# IFB-40003-R01_-_I2C_Buttons.net
KiCad netlist of a schematic drawn in EAGLE
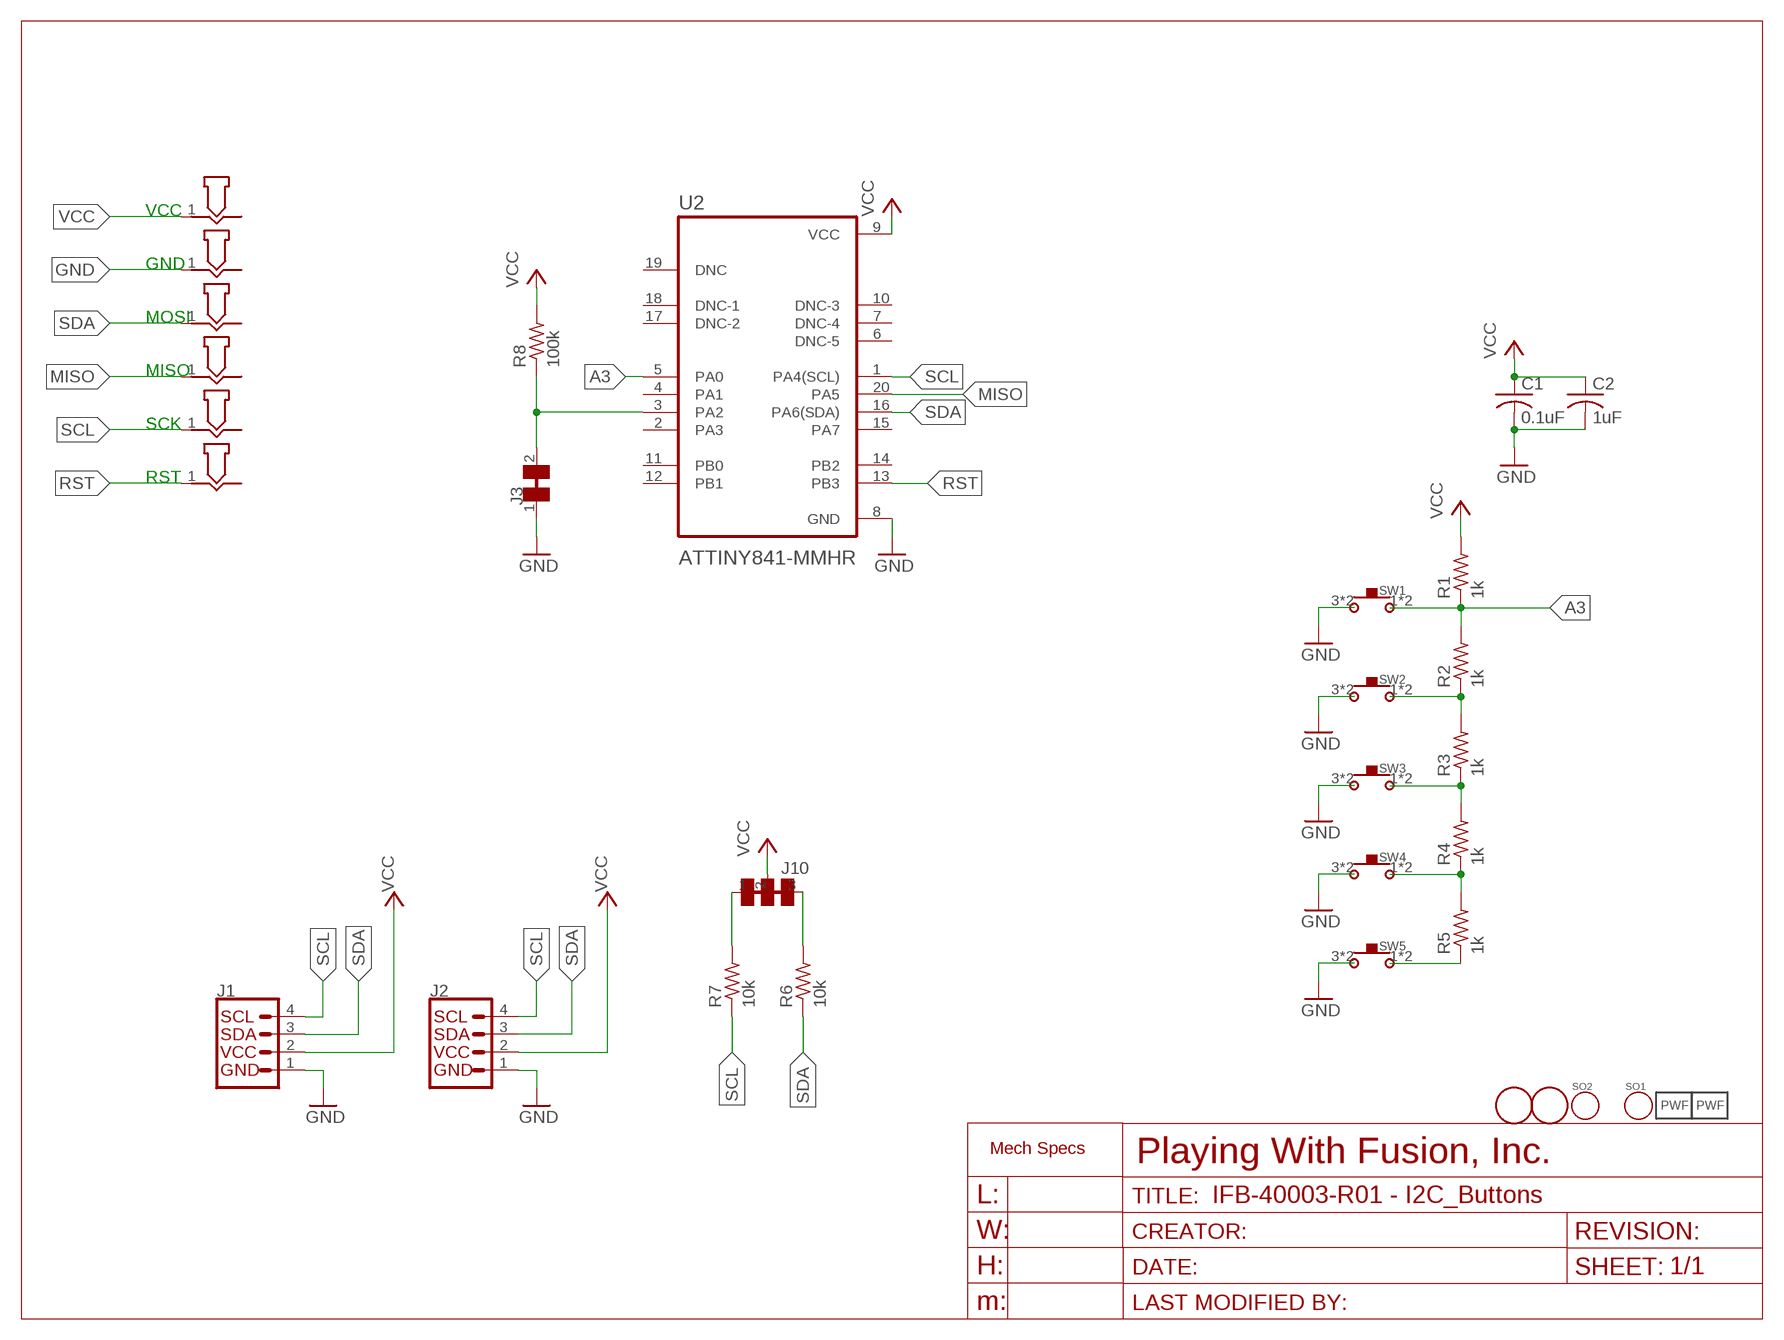
[diagram p0: schematic, sheet 1]

(export (version "E")
  (design (tool "Eeschema 10.0.6"))
  (components
    (comp (ref "C1")
      (value "0.1uF")
      (footprint "eagle-import:C0603K")
      (libsource (lib "eagle-import") (part "C-USC0603K"))
    )
    (comp (ref "C2")
      (value "1uF")
      (footprint "eagle-import:C0603K")
      (libsource (lib "eagle-import") (part "C-USC0603K"))
    )
    (comp (ref "J1")
      (value "QWIIC_CONNECTORJS-1MM")
      (footprint "eagle-import:1X04_1MM_RA")
      (libsource (lib "eagle-import") (part "QWIIC_CONNECTORJS-1MM"))
    )
    (comp (ref "J2")
      (value "QWIIC_CONNECTORJS-1MM")
      (footprint "eagle-import:1X04_1MM_RA")
      (libsource (lib "eagle-import") (part "QWIIC_CONNECTORJS-1MM"))
    )
    (comp (ref "J3")
      (value "CUTTABLE_JUMPER")
      (footprint "eagle-import:SMT_CUTTABLE_JUMPER")
      (libsource (lib "eagle-import") (part "CUTTABLE_JUMPER"))
    )
    (comp (ref "J4")
      (value "POGO_PAD")
      (footprint "eagle-import:P50_POGO_BOARD_CONTACT_12MIL")
      (libsource (lib "eagle-import") (part "POGO_PAD"))
    )
    (comp (ref "J5")
      (value "POGO_PAD")
      (footprint "eagle-import:P50_POGO_BOARD_CONTACT_12MIL")
      (libsource (lib "eagle-import") (part "POGO_PAD"))
    )
    (comp (ref "J6")
      (value "POGO_PAD")
      (footprint "eagle-import:P50_POGO_BOARD_CONTACT_12MIL")
      (libsource (lib "eagle-import") (part "POGO_PAD"))
    )
    (comp (ref "J7")
      (value "POGO_PAD")
      (footprint "eagle-import:P50_POGO_BOARD_CONTACT_12MIL")
      (libsource (lib "eagle-import") (part "POGO_PAD"))
    )
    (comp (ref "J8")
      (value "POGO_PAD")
      (footprint "eagle-import:P50_POGO_BOARD_CONTACT_12MIL")
      (libsource (lib "eagle-import") (part "POGO_PAD"))
    )
    (comp (ref "J9")
      (value "POGO_PAD")
      (footprint "eagle-import:P50_POGO_BOARD_CONTACT_12MIL")
      (libsource (lib "eagle-import") (part "POGO_PAD"))
    )
    (comp (ref "J10")
      (value "CUT_JUMPER_2X")
      (footprint "eagle-import:SMT_2X_CUTTABLE_JUMPER")
      (libsource (lib "eagle-import") (part "CUT_JUMPER_2X"))
    )
    (comp (ref "LOGO1")
      (value "PWF_LOGOPWF-6MM-SS")
      (footprint "eagle-import:LOGO_6MM_STEIN")
      (libsource (lib "eagle-import") (part "PWF_LOGOPWF-6MM-SS"))
    )
    (comp (ref "LOGO2")
      (value "PWF_LOGOPWF-12MM-SS")
      (footprint "eagle-import:LOGO_12MM_STEIN")
      (libsource (lib "eagle-import") (part "PWF_LOGOPWF-12MM-SS"))
    )
    (comp (ref "R1")
      (value "1k")
      (footprint "eagle-import:R0603")
      (libsource (lib "eagle-import") (part "R-US_R0603"))
    )
    (comp (ref "R2")
      (value "1k")
      (footprint "eagle-import:R0603")
      (libsource (lib "eagle-import") (part "R-US_R0603"))
    )
    (comp (ref "R3")
      (value "1k")
      (footprint "eagle-import:R0603")
      (libsource (lib "eagle-import") (part "R-US_R0603"))
    )
    (comp (ref "R4")
      (value "1k")
      (footprint "eagle-import:R0603")
      (libsource (lib "eagle-import") (part "R-US_R0603"))
    )
    (comp (ref "R5")
      (value "1k")
      (footprint "eagle-import:R0603")
      (libsource (lib "eagle-import") (part "R-US_R0603"))
    )
    (comp (ref "R6")
      (value "10k")
      (footprint "eagle-import:R0603")
      (libsource (lib "eagle-import") (part "R-US_R0603"))
    )
    (comp (ref "R7")
      (value "10k")
      (footprint "eagle-import:R0603")
      (libsource (lib "eagle-import") (part "R-US_R0603"))
    )
    (comp (ref "R8")
      (value "100k")
      (footprint "eagle-import:R0603")
      (libsource (lib "eagle-import") (part "R-US_R0603"))
    )
    (comp (ref "SO1")
      (value "STAND_OFFNO4_TIGHT")
      (footprint "eagle-import:STANDOFF_NO4_TIGHT")
      (libsource (lib "eagle-import") (part "STAND_OFFNO4_TIGHT"))
    )
    (comp (ref "SO2")
      (value "STAND_OFFNO4_TIGHT")
      (footprint "eagle-import:STANDOFF_NO4_TIGHT")
      (libsource (lib "eagle-import") (part "STAND_OFFNO4_TIGHT"))
    )
    (comp (ref "SW1")
      (value "PTS6455MM")
      (footprint "eagle-import:PTS645_5MM")
      (libsource (lib "eagle-import") (part "PTS6455MM"))
    )
    (comp (ref "SW2")
      (value "PTS6455MM")
      (footprint "eagle-import:PTS645_5MM")
      (libsource (lib "eagle-import") (part "PTS6455MM"))
    )
    (comp (ref "SW3")
      (value "PTS6455MM")
      (footprint "eagle-import:PTS645_5MM")
      (libsource (lib "eagle-import") (part "PTS6455MM"))
    )
    (comp (ref "SW4")
      (value "PTS6455MM")
      (footprint "eagle-import:PTS645_5MM")
      (libsource (lib "eagle-import") (part "PTS6455MM"))
    )
    (comp (ref "SW5")
      (value "PTS6455MM")
      (footprint "eagle-import:PTS645_5MM")
      (libsource (lib "eagle-import") (part "PTS6455MM"))
    )
    (comp (ref "U$2")
      (value "FIDUCIAL")
      (footprint "eagle-import:FIDUCIAL_1MM")
      (libsource (lib "eagle-import") (part "FIDUCIAL"))
    )
    (comp (ref "U$3")
      (value "FIDUCIAL")
      (footprint "eagle-import:FIDUCIAL_1MM")
      (libsource (lib "eagle-import") (part "FIDUCIAL"))
    )
    (comp (ref "U2")
      (value "ATTINY841-MMHR")
      (footprint "eagle-import:QFN45P300X300X85-21N")
      (fields (field (name "MF") "Microchip"))
      (libsource (lib "eagle-import") (part "ATTINY841-MMHR"))
    )
  )
  (nets
    (net (code "1") (name "A3") (class "Default")
      (node (ref "R1") (pin "1") (pinfunction "1_1") (pintype "passive"))
      (node (ref "R2") (pin "2") (pinfunction "2_2") (pintype "passive"))
      (node (ref "SW1") (pin "1") (pinfunction "1_1") (pintype "bidirectional"))
      (node (ref "SW1") (pin "2") (pinfunction "1_2") (pintype "bidirectional"))
      (node (ref "U2") (pin "5") (pinfunction "PA0_5") (pintype "bidirectional"))
    )
    (net (code "2") (name "GND") (class "Default")
      (node (ref "C1") (pin "2") (pinfunction "2_2") (pintype "passive"))
      (node (ref "C2") (pin "2") (pinfunction "2_2") (pintype "passive"))
      (node (ref "J1") (pin "1") (pinfunction "GND_1") (pintype "power_in"))
      (node (ref "J2") (pin "1") (pinfunction "GND_1") (pintype "power_in"))
      (node (ref "J3") (pin "1") (pinfunction "1_1") (pintype "bidirectional"))
      (node (ref "J5") (pin "1") (pinfunction "P$1_1") (pintype "bidirectional"))
      (node (ref "SW1") (pin "3") (pinfunction "3_3") (pintype "bidirectional"))
      (node (ref "SW1") (pin "4") (pinfunction "3_4") (pintype "bidirectional"))
      (node (ref "SW2") (pin "3") (pinfunction "3_3") (pintype "bidirectional"))
      (node (ref "SW2") (pin "4") (pinfunction "3_4") (pintype "bidirectional"))
      (node (ref "SW3") (pin "3") (pinfunction "3_3") (pintype "bidirectional"))
      (node (ref "SW3") (pin "4") (pinfunction "3_4") (pintype "bidirectional"))
      (node (ref "SW4") (pin "3") (pinfunction "3_3") (pintype "bidirectional"))
      (node (ref "SW4") (pin "4") (pinfunction "3_4") (pintype "bidirectional"))
      (node (ref "SW5") (pin "3") (pinfunction "3_3") (pintype "bidirectional"))
      (node (ref "SW5") (pin "4") (pinfunction "3_4") (pintype "bidirectional"))
      (node (ref "U2") (pin "8") (pinfunction "GND_8") (pintype "power_in"))
    )
    (net (code "3") (name "MISO") (class "Default")
      (node (ref "J7") (pin "1") (pinfunction "P$1_1") (pintype "bidirectional"))
      (node (ref "U2") (pin "20") (pinfunction "PA5_20") (pintype "bidirectional"))
    )
    (net (code "4") (name "Net-(J10-Pad1)") (class "Default")
      (node (ref "J10") (pin "1") (pinfunction "1_1") (pintype "bidirectional"))
      (node (ref "R7") (pin "2") (pinfunction "2_2") (pintype "passive"))
    )
    (net (code "5") (name "Net-(J10-Pad3)") (class "Default")
      (node (ref "J10") (pin "3") (pinfunction "3_3") (pintype "bidirectional"))
      (node (ref "R6") (pin "2") (pinfunction "2_2") (pintype "passive"))
    )
    (net (code "6") (name "Net-(R2-Pad1)") (class "Default")
      (node (ref "R2") (pin "1") (pinfunction "1_1") (pintype "passive"))
      (node (ref "R3") (pin "2") (pinfunction "2_2") (pintype "passive"))
      (node (ref "SW2") (pin "1") (pinfunction "1_1") (pintype "bidirectional"))
      (node (ref "SW2") (pin "2") (pinfunction "1_2") (pintype "bidirectional"))
    )
    (net (code "7") (name "Net-(R3-Pad1)") (class "Default")
      (node (ref "R3") (pin "1") (pinfunction "1_1") (pintype "passive"))
      (node (ref "R4") (pin "2") (pinfunction "2_2") (pintype "passive"))
      (node (ref "SW3") (pin "1") (pinfunction "1_1") (pintype "bidirectional"))
      (node (ref "SW3") (pin "2") (pinfunction "1_2") (pintype "bidirectional"))
    )
    (net (code "8") (name "Net-(R4-Pad1)") (class "Default")
      (node (ref "R4") (pin "1") (pinfunction "1_1") (pintype "passive"))
      (node (ref "R5") (pin "2") (pinfunction "2_2") (pintype "passive"))
      (node (ref "SW4") (pin "1") (pinfunction "1_1") (pintype "bidirectional"))
      (node (ref "SW4") (pin "2") (pinfunction "1_2") (pintype "bidirectional"))
    )
    (net (code "9") (name "Net-(R5-Pad1)") (class "Default")
      (node (ref "R5") (pin "1") (pinfunction "1_1") (pintype "passive"))
      (node (ref "SW5") (pin "1") (pinfunction "1_1") (pintype "bidirectional"))
      (node (ref "SW5") (pin "2") (pinfunction "1_2") (pintype "bidirectional"))
    )
    (net (code "10") (name "Net-(U2-PA2)") (class "Default")
      (node (ref "J3") (pin "2") (pinfunction "2_2") (pintype "bidirectional"))
      (node (ref "R8") (pin "1") (pinfunction "1_1") (pintype "passive"))
      (node (ref "U2") (pin "3") (pinfunction "PA2_3") (pintype "bidirectional"))
    )
    (net (code "11") (name "RST") (class "Default")
      (node (ref "J9") (pin "1") (pinfunction "P$1_1") (pintype "bidirectional"))
      (node (ref "U2") (pin "13") (pinfunction "PB3_13") (pintype "bidirectional"))
    )
    (net (code "12") (name "SCL") (class "Default")
      (node (ref "J1") (pin "4") (pinfunction "SCL_4") (pintype "passive"))
      (node (ref "J2") (pin "4") (pinfunction "SCL_4") (pintype "passive"))
      (node (ref "J8") (pin "1") (pinfunction "P$1_1") (pintype "bidirectional"))
      (node (ref "R7") (pin "1") (pinfunction "1_1") (pintype "passive"))
      (node (ref "U2") (pin "1") (pinfunction "PA4(SCL)_1") (pintype "bidirectional"))
    )
    (net (code "13") (name "SDA") (class "Default")
      (node (ref "J1") (pin "3") (pinfunction "SDA_3") (pintype "passive"))
      (node (ref "J2") (pin "3") (pinfunction "SDA_3") (pintype "passive"))
      (node (ref "J6") (pin "1") (pinfunction "P$1_1") (pintype "bidirectional"))
      (node (ref "R6") (pin "1") (pinfunction "1_1") (pintype "passive"))
      (node (ref "U2") (pin "16") (pinfunction "PA6(SDA)_16") (pintype "bidirectional"))
    )
    (net (code "14") (name "VCC") (class "Default")
      (node (ref "C1") (pin "1") (pinfunction "1_1") (pintype "passive"))
      (node (ref "C2") (pin "1") (pinfunction "1_1") (pintype "passive"))
      (node (ref "J1") (pin "2") (pinfunction "VCC_2") (pintype "power_in"))
      (node (ref "J10") (pin "2") (pinfunction "2_2") (pintype "bidirectional"))
      (node (ref "J2") (pin "2") (pinfunction "VCC_2") (pintype "power_in"))
      (node (ref "J4") (pin "1") (pinfunction "P$1_1") (pintype "bidirectional"))
      (node (ref "R1") (pin "2") (pinfunction "2_2") (pintype "passive"))
      (node (ref "R8") (pin "2") (pinfunction "2_2") (pintype "passive"))
      (node (ref "U2") (pin "9") (pinfunction "VCC_9") (pintype "power_in"))
    )
    (net (code "15") (name "unconnected-(U2-DNC-1-Pad18)") (class "Default")
      (node (ref "U2") (pin "18") (pinfunction "DNC-1_18") (pintype "bidirectional"))
    )
    (net (code "16") (name "unconnected-(U2-DNC-2-Pad17)") (class "Default")
      (node (ref "U2") (pin "17") (pinfunction "DNC-2_17") (pintype "bidirectional"))
    )
    (net (code "17") (name "unconnected-(U2-DNC-3-Pad10)") (class "Default")
      (node (ref "U2") (pin "10") (pinfunction "DNC-3_10") (pintype "bidirectional"))
    )
    (net (code "18") (name "unconnected-(U2-DNC-4-Pad7)") (class "Default")
      (node (ref "U2") (pin "7") (pinfunction "DNC-4_7") (pintype "bidirectional"))
    )
    (net (code "19") (name "unconnected-(U2-DNC-5-Pad6)") (class "Default")
      (node (ref "U2") (pin "6") (pinfunction "DNC-5_6") (pintype "bidirectional"))
    )
    (net (code "20") (name "unconnected-(U2-DNC-Pad19)") (class "Default")
      (node (ref "U2") (pin "19") (pinfunction "DNC_19") (pintype "bidirectional"))
    )
    (net (code "21") (name "unconnected-(U2-PA1-Pad4)") (class "Default")
      (node (ref "U2") (pin "4") (pinfunction "PA1_4") (pintype "bidirectional"))
    )
    (net (code "22") (name "unconnected-(U2-PA3-Pad2)") (class "Default")
      (node (ref "U2") (pin "2") (pinfunction "PA3_2") (pintype "bidirectional"))
    )
    (net (code "23") (name "unconnected-(U2-PA7-Pad15)") (class "Default")
      (node (ref "U2") (pin "15") (pinfunction "PA7_15") (pintype "bidirectional"))
    )
    (net (code "24") (name "unconnected-(U2-PB0-Pad11)") (class "Default")
      (node (ref "U2") (pin "11") (pinfunction "PB0_11") (pintype "bidirectional"))
    )
    (net (code "25") (name "unconnected-(U2-PB1-Pad12)") (class "Default")
      (node (ref "U2") (pin "12") (pinfunction "PB1_12") (pintype "bidirectional"))
    )
    (net (code "26") (name "unconnected-(U2-PB2-Pad14)") (class "Default")
      (node (ref "U2") (pin "14") (pinfunction "PB2_14") (pintype "bidirectional"))
    )
  )
)
